# CYAN_EVSE_Logic_board_v1_3.net
KiCad netlist of a schematic drawn in Altium Designer
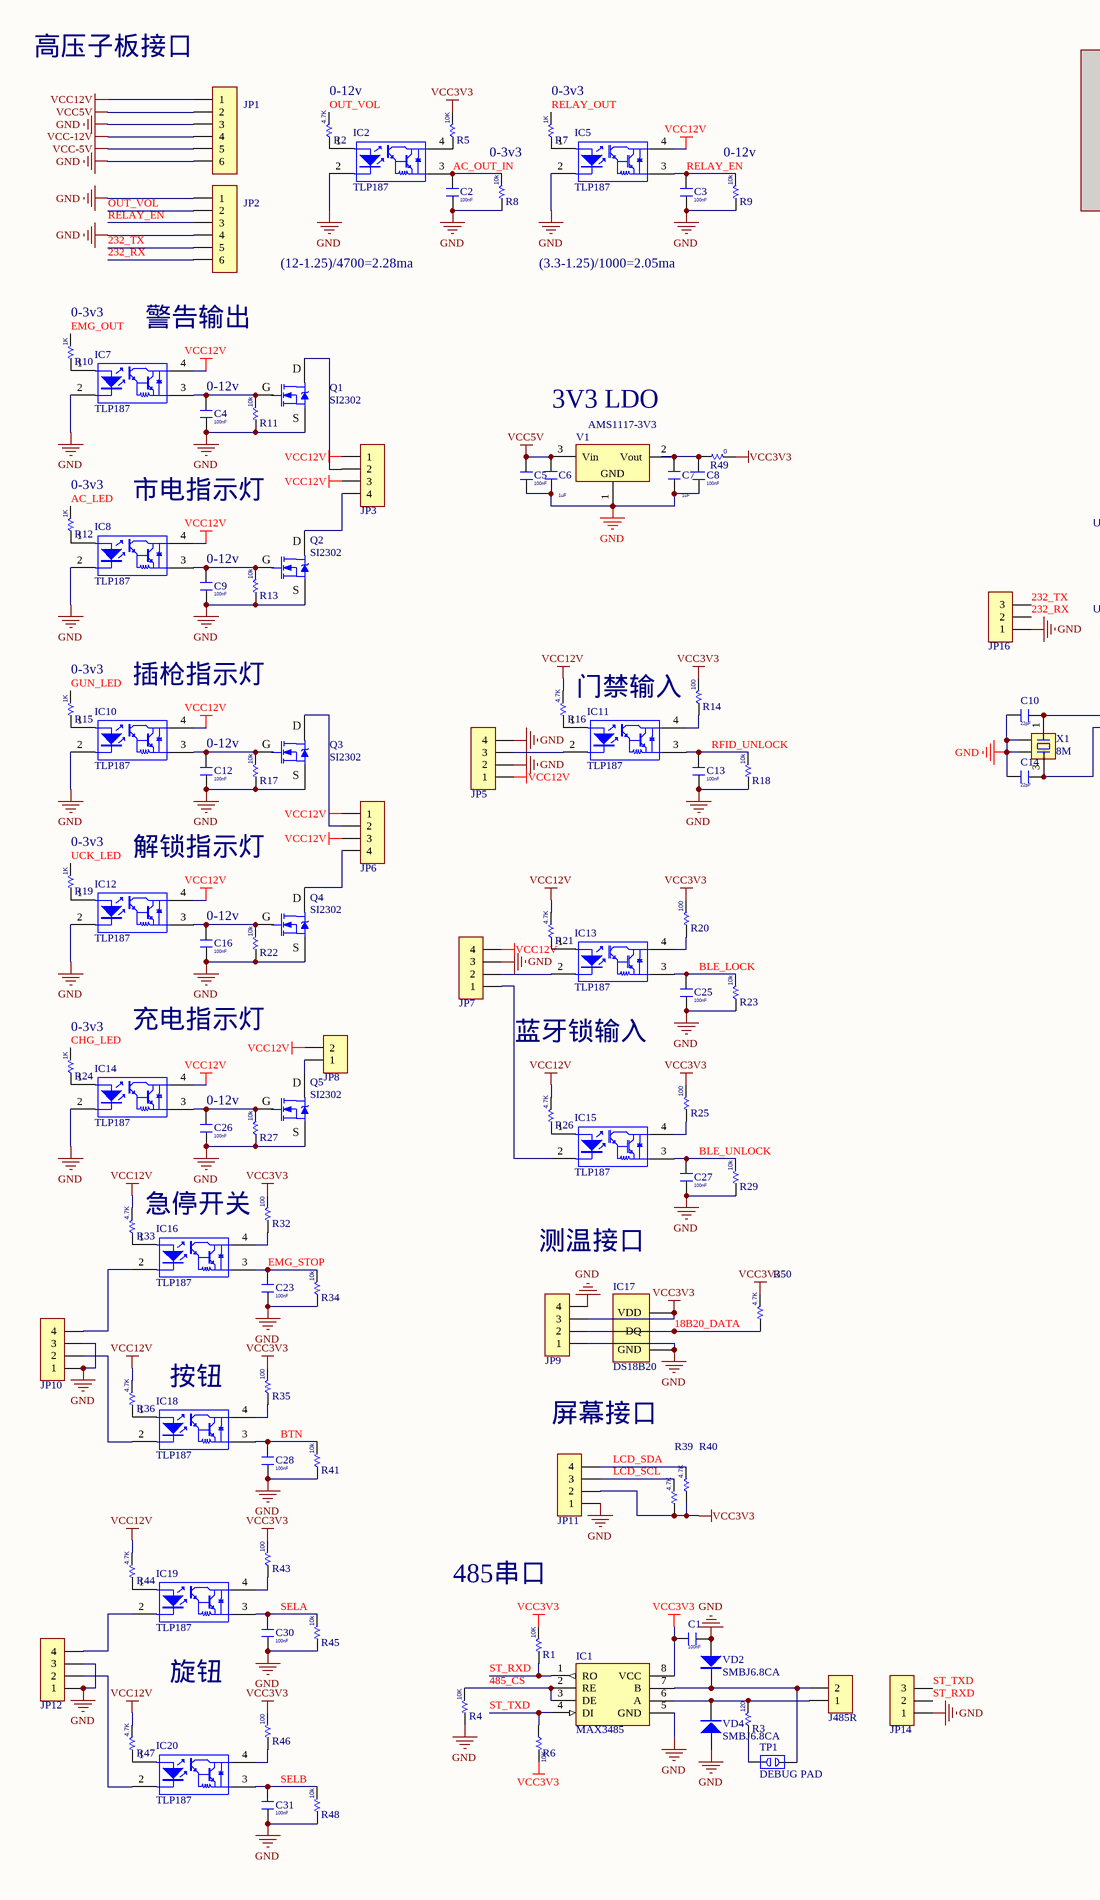
[diagram p0: CYAN_EVSE_Logic_board_v1.3.SchDoc, left]
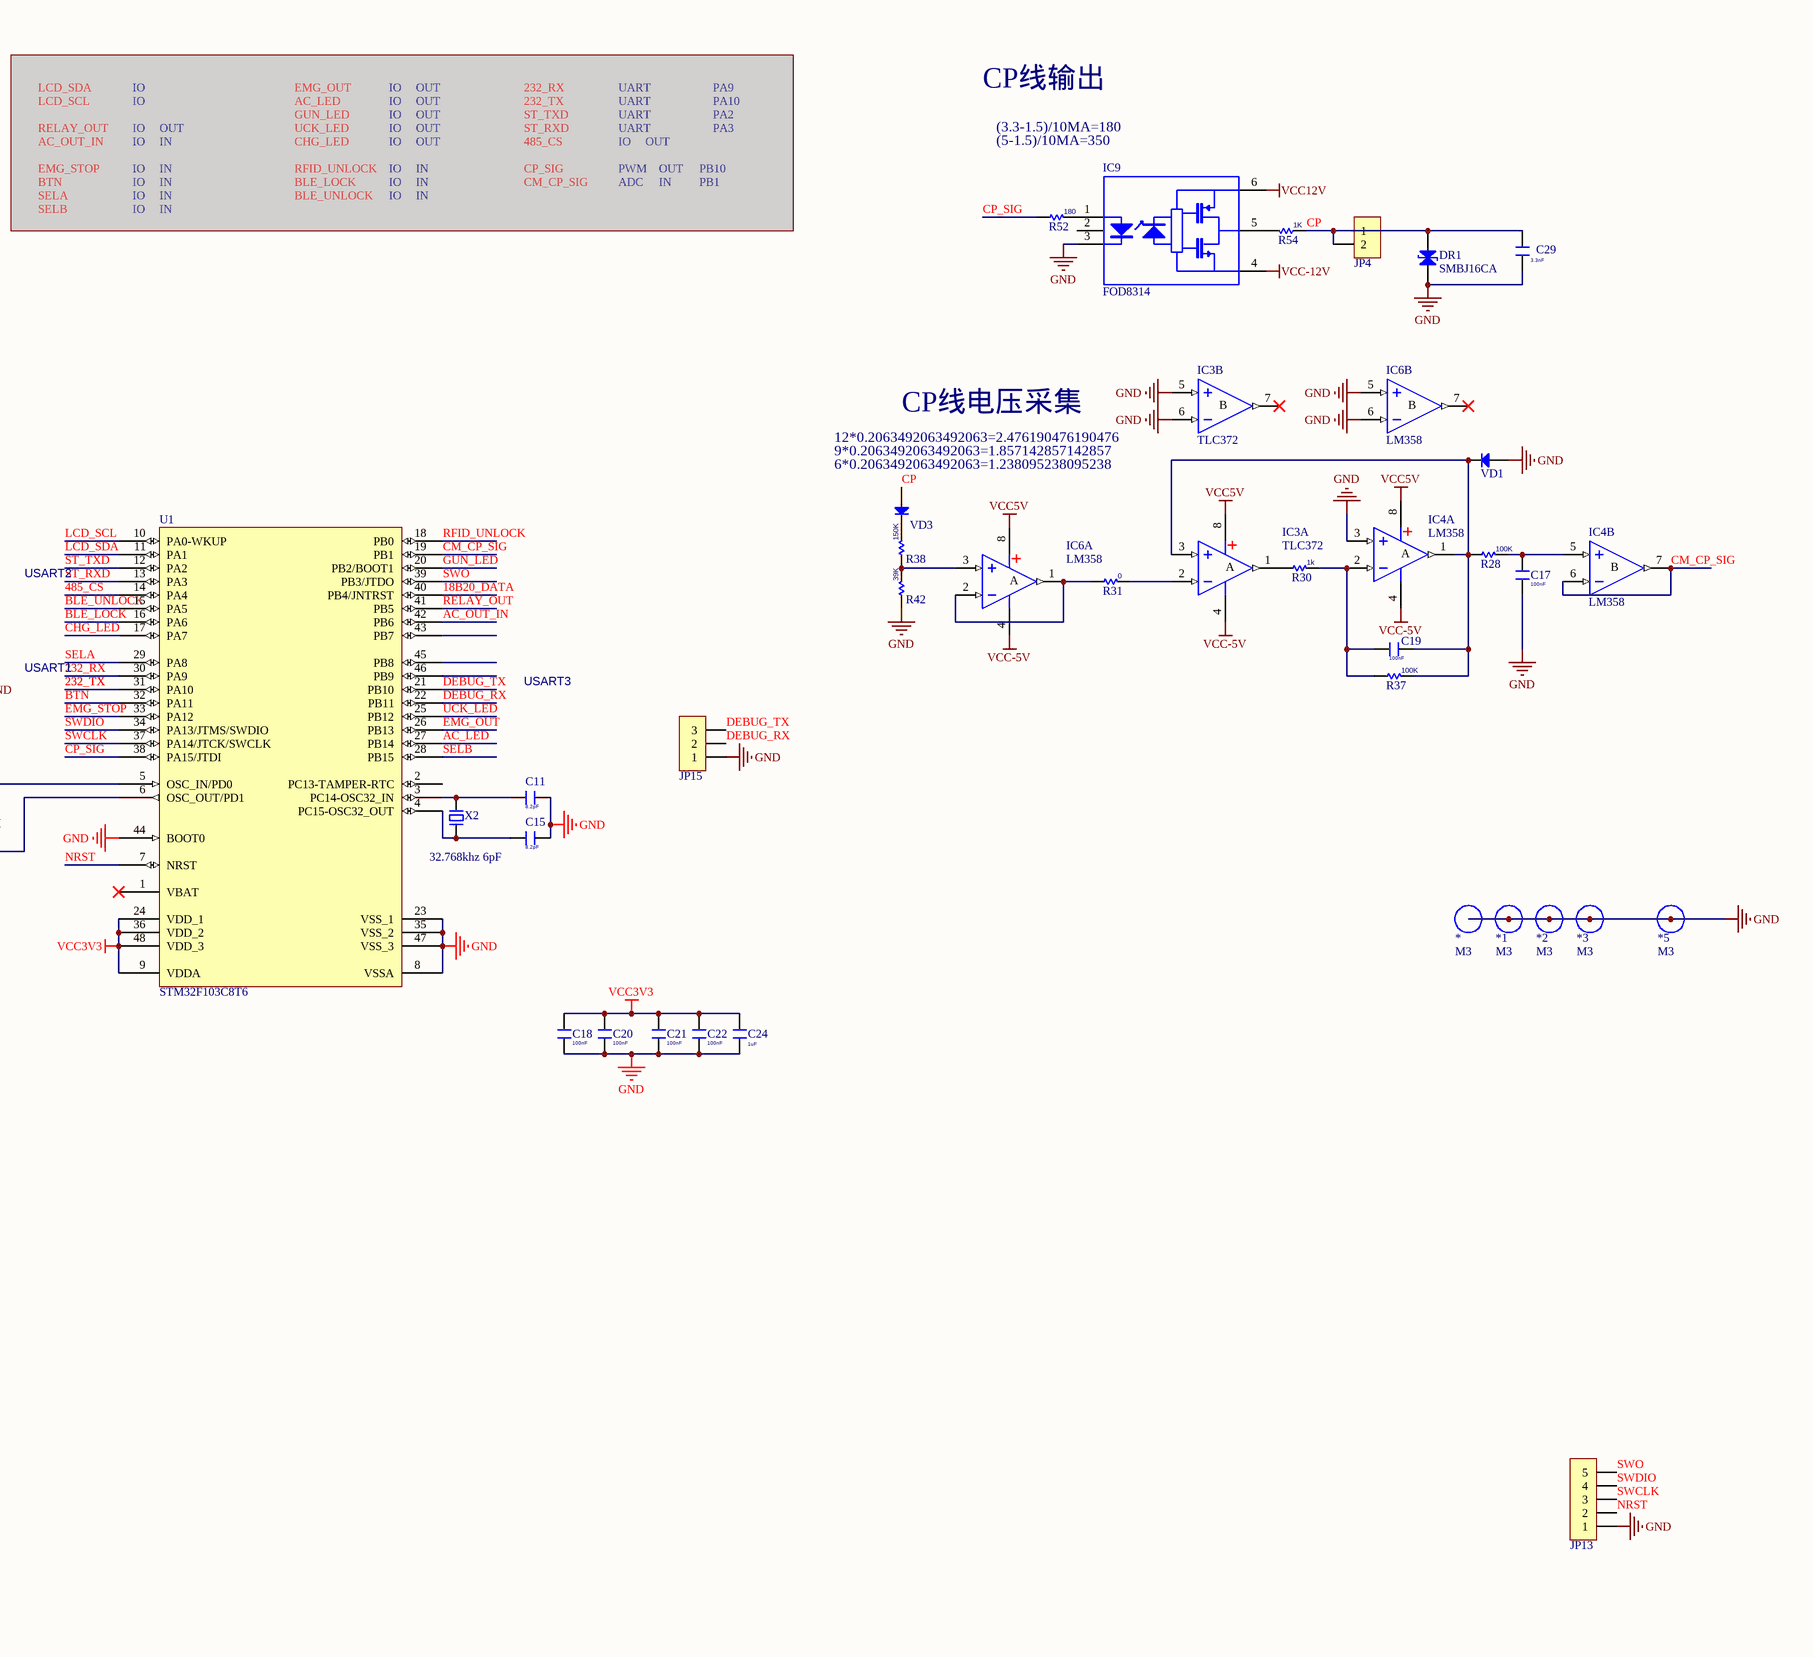
[diagram p1: CYAN_EVSE_Logic_board_v1.3.SchDoc, right]

(export (version "E")
  (design (tool "Eeschema 10.0.6"))
  (components
    (comp (ref "*")
      (value "M3")
      (footprint "M3 125X300")
      (description "铜柱孔")
      (libsource (lib "未分类器件") (part "M3"))
    )
    (comp (ref "*1")
      (value "M3")
      (footprint "M3 125X300")
      (description "铜柱孔")
      (libsource (lib "未分类器件") (part "M3"))
    )
    (comp (ref "*2")
      (value "M3")
      (footprint "M3 125X300")
      (description "铜柱孔")
      (libsource (lib "未分类器件") (part "M3"))
    )
    (comp (ref "*3")
      (value "M3")
      (footprint "M3 125X300")
      (description "铜柱孔")
      (libsource (lib "未分类器件") (part "M3"))
    )
    (comp (ref "*5")
      (value "M3")
      (footprint "M3 125X300")
      (description "铜柱孔")
      (libsource (lib "未分类器件") (part "M3"))
    )
    (comp (ref "C1")
      (value "100nF")
      (footprint "C 0805")
      (description "无极性贴片电容")
      (fields (field (name "VOLTAGE") "20V") (field (name "Comment") "C"))
      (libsource (lib "电阻-电容-电感") (part "C"))
    )
    (comp (ref "C2")
      (value "100nF")
      (footprint "C 0805")
      (description "无极性贴片电容")
      (fields (field (name "VOLTAGE") "20V") (field (name "Comment") "C"))
      (libsource (lib "电阻-电容-电感") (part "C"))
    )
    (comp (ref "C3")
      (value "100nF")
      (footprint "C 0805")
      (description "无极性贴片电容")
      (fields (field (name "VOLTAGE") "20V") (field (name "Comment") "C"))
      (libsource (lib "电阻-电容-电感") (part "C"))
    )
    (comp (ref "C4")
      (value "100nF")
      (footprint "C 0805")
      (description "无极性贴片电容")
      (fields (field (name "VOLTAGE") "20V") (field (name "Comment") "C"))
      (libsource (lib "电阻-电容-电感") (part "C"))
    )
    (comp (ref "C5")
      (value "100nF")
      (footprint "C 0805")
      (description "无极性贴片电容")
      (fields (field (name "VOLTAGE") "20V") (field (name "Comment") "C"))
      (libsource (lib "电阻-电容-电感") (part "C"))
    )
    (comp (ref "C6")
      (value "1uF")
      (footprint "C 0805")
      (description "无极性贴片电容")
      (fields (field (name "Comment") "C"))
      (libsource (lib "电阻-电容-电感") (part "C"))
    )
    (comp (ref "C7")
      (value "1uF")
      (footprint "C 0805")
      (description "无极性贴片电容")
      (fields (field (name "Comment") "C"))
      (libsource (lib "电阻-电容-电感") (part "C"))
    )
    (comp (ref "C8")
      (value "100nF")
      (footprint "C 0805")
      (description "无极性贴片电容")
      (fields (field (name "VOLTAGE") "20V") (field (name "Comment") "C"))
      (libsource (lib "电阻-电容-电感") (part "C"))
    )
    (comp (ref "C9")
      (value "100nF")
      (footprint "C 0805")
      (description "无极性贴片电容")
      (fields (field (name "VOLTAGE") "20V") (field (name "Comment") "C"))
      (libsource (lib "电阻-电容-电感") (part "C"))
    )
    (comp (ref "C10")
      (value "22pF")
      (footprint "C 0805")
      (description "无极性贴片电容")
      (fields (field (name "VOLTAGE") "20V") (field (name "Comment") "C"))
      (libsource (lib "电阻-电容-电感") (part "C"))
    )
    (comp (ref "C11")
      (value "8.2pF")
      (footprint "C 0805")
      (description "无极性贴片电容")
      (fields (field (name "VOLTAGE") "20V") (field (name "Comment") "C"))
      (libsource (lib "电阻-电容-电感") (part "C"))
    )
    (comp (ref "C12")
      (value "100nF")
      (footprint "C 0805")
      (description "无极性贴片电容")
      (fields (field (name "VOLTAGE") "20V") (field (name "Comment") "C"))
      (libsource (lib "电阻-电容-电感") (part "C"))
    )
    (comp (ref "C13")
      (value "100nF")
      (footprint "C 0805")
      (description "无极性贴片电容")
      (fields (field (name "VOLTAGE") "20V") (field (name "Comment") "C"))
      (libsource (lib "电阻-电容-电感") (part "C"))
    )
    (comp (ref "C14")
      (value "22pF")
      (footprint "C 0805")
      (description "无极性贴片电容")
      (fields (field (name "VOLTAGE") "20V") (field (name "Comment") "C"))
      (libsource (lib "电阻-电容-电感") (part "C"))
    )
    (comp (ref "C15")
      (value "8.2pF")
      (footprint "C 0805")
      (description "无极性贴片电容")
      (fields (field (name "VOLTAGE") "20V") (field (name "Comment") "C"))
      (libsource (lib "电阻-电容-电感") (part "C"))
    )
    (comp (ref "C16")
      (value "100nF")
      (footprint "C 0805")
      (description "无极性贴片电容")
      (fields (field (name "VOLTAGE") "20V") (field (name "Comment") "C"))
      (libsource (lib "电阻-电容-电感") (part "C"))
    )
    (comp (ref "C17")
      (value "100nF")
      (footprint "C 0805")
      (description "无极性贴片电容")
      (fields (field (name "VOLTAGE") "20V") (field (name "Comment") "C"))
      (libsource (lib "电阻-电容-电感") (part "C"))
    )
    (comp (ref "C18")
      (value "100nF")
      (footprint "C 0805")
      (description "无极性贴片电容")
      (fields (field (name "VOLTAGE") "20V") (field (name "Comment") "C"))
      (libsource (lib "电阻-电容-电感") (part "C"))
    )
    (comp (ref "C19")
      (value "100nF")
      (footprint "C 0805")
      (description "无极性贴片电容")
      (fields (field (name "VOLTAGE") "20V") (field (name "Comment") "C"))
      (libsource (lib "电阻-电容-电感") (part "C"))
    )
    (comp (ref "C20")
      (value "100nF")
      (footprint "C 0805")
      (description "无极性贴片电容")
      (fields (field (name "VOLTAGE") "20V") (field (name "Comment") "C"))
      (libsource (lib "电阻-电容-电感") (part "C"))
    )
    (comp (ref "C21")
      (value "100nF")
      (footprint "C 0805")
      (description "无极性贴片电容")
      (fields (field (name "VOLTAGE") "20V") (field (name "Comment") "C"))
      (libsource (lib "电阻-电容-电感") (part "C"))
    )
    (comp (ref "C22")
      (value "100nF")
      (footprint "C 0805")
      (description "无极性贴片电容")
      (fields (field (name "VOLTAGE") "20V") (field (name "Comment") "C"))
      (libsource (lib "电阻-电容-电感") (part "C"))
    )
    (comp (ref "C23")
      (value "100nF")
      (footprint "C 0805")
      (description "无极性贴片电容")
      (fields (field (name "VOLTAGE") "20V") (field (name "Comment") "C"))
      (libsource (lib "电阻-电容-电感") (part "C"))
    )
    (comp (ref "C24")
      (value "1uF")
      (footprint "C 0805")
      (description "无极性贴片电容")
      (fields (field (name "Comment") "C"))
      (libsource (lib "电阻-电容-电感") (part "C"))
    )
    (comp (ref "C25")
      (value "100nF")
      (footprint "C 0805")
      (description "无极性贴片电容")
      (fields (field (name "VOLTAGE") "20V") (field (name "Comment") "C"))
      (libsource (lib "电阻-电容-电感") (part "C"))
    )
    (comp (ref "C26")
      (value "100nF")
      (footprint "C 0805")
      (description "无极性贴片电容")
      (fields (field (name "VOLTAGE") "20V") (field (name "Comment") "C"))
      (libsource (lib "电阻-电容-电感") (part "C"))
    )
    (comp (ref "C27")
      (value "100nF")
      (footprint "C 0805")
      (description "无极性贴片电容")
      (fields (field (name "VOLTAGE") "20V") (field (name "Comment") "C"))
      (libsource (lib "电阻-电容-电感") (part "C"))
    )
    (comp (ref "C28")
      (value "100nF")
      (footprint "C 0805")
      (description "无极性贴片电容")
      (fields (field (name "VOLTAGE") "20V") (field (name "Comment") "C"))
      (libsource (lib "电阻-电容-电感") (part "C"))
    )
    (comp (ref "C29")
      (value "3.3nF")
      (footprint "C 1206")
      (description "无极性贴片电容")
      (fields (field (name "VOLTAGE") "50V") (field (name "Comment") "C"))
      (libsource (lib "电阻-电容-电感") (part "C"))
    )
    (comp (ref "C30")
      (value "100nF")
      (footprint "C 0805")
      (description "无极性贴片电容")
      (fields (field (name "VOLTAGE") "20V") (field (name "Comment") "C"))
      (libsource (lib "电阻-电容-电感") (part "C"))
    )
    (comp (ref "C31")
      (value "100nF")
      (footprint "C 0805")
      (description "无极性贴片电容")
      (fields (field (name "VOLTAGE") "20V") (field (name "Comment") "C"))
      (libsource (lib "电阻-电容-电感") (part "C"))
    )
    (comp (ref "DR1")
      (value "SMBJ16CA")
      (footprint "SMB")
      (description "瞬态电压抑制二极管")
      (libsource (lib "二极管-整流桥") (part "DR"))
    )
    (comp (ref "IC1")
      (value "MAX3485")
      (footprint "SOP8_N")
      (description "RS485总线收发芯片")
      (libsource (lib "IC芯片") (part "MAX487"))
    )
    (comp (ref "IC2")
      (value "TLP187")
      (footprint "SOP6_4.6MM_W1.27_4PIN_N")
      (description "达林顿输出光耦")
      (libsource (lib "传感元件") (part "TLP187"))
    )
    (comp (ref "IC3")
      (value "TLC372")
      (footprint "SOP8_N")
      (description "双路电压比较,MOS下臂输出")
      (libsource (lib "IC芯片") (part "TLC372"))
    )
    (comp (ref "IC4")
      (value "LM358")
      (footprint "SOP8_N")
      (description "双路运放")
      (libsource (lib "IC芯片") (part "LM358"))
    )
    (comp (ref "IC5")
      (value "TLP187")
      (footprint "SOP6_4.6MM_W1.27_4PIN_N")
      (description "达林顿输出光耦")
      (libsource (lib "传感元件") (part "TLP187"))
    )
    (comp (ref "IC6")
      (value "LM358")
      (footprint "SOP8_N")
      (description "双路运放")
      (libsource (lib "IC芯片") (part "LM358"))
    )
    (comp (ref "IC7")
      (value "TLP187")
      (footprint "SOP6_4.6MM_W1.27_4PIN_N")
      (description "达林顿输出光耦")
      (libsource (lib "传感元件") (part "TLP187"))
    )
    (comp (ref "IC8")
      (value "TLP187")
      (footprint "SOP6_4.6MM_W1.27_4PIN_N")
      (description "达林顿输出光耦")
      (libsource (lib "传感元件") (part "TLP187"))
    )
    (comp (ref "IC9")
      (value "FOD8314")
      (footprint "SOP6_7MM_WIDE_LEAD_N")
      (description "MOSFET/IGBT 驱动光耦，15-30v 1a")
      (libsource (lib "传感元件") (part "FOD8314"))
    )
    (comp (ref "IC10")
      (value "TLP187")
      (footprint "SOP6_4.6MM_W1.27_4PIN_N")
      (description "达林顿输出光耦")
      (libsource (lib "传感元件") (part "TLP187"))
    )
    (comp (ref "IC11")
      (value "TLP187")
      (footprint "SOP6_4.6MM_W1.27_4PIN_N")
      (description "达林顿输出光耦")
      (libsource (lib "传感元件") (part "TLP187"))
    )
    (comp (ref "IC12")
      (value "TLP187")
      (footprint "SOP6_4.6MM_W1.27_4PIN_N")
      (description "达林顿输出光耦")
      (libsource (lib "传感元件") (part "TLP187"))
    )
    (comp (ref "IC13")
      (value "TLP187")
      (footprint "SOP6_4.6MM_W1.27_4PIN_N")
      (description "达林顿输出光耦")
      (libsource (lib "传感元件") (part "TLP187"))
    )
    (comp (ref "IC14")
      (value "TLP187")
      (footprint "SOP6_4.6MM_W1.27_4PIN_N")
      (description "达林顿输出光耦")
      (libsource (lib "传感元件") (part "TLP187"))
    )
    (comp (ref "IC15")
      (value "TLP187")
      (footprint "SOP6_4.6MM_W1.27_4PIN_N")
      (description "达林顿输出光耦")
      (libsource (lib "传感元件") (part "TLP187"))
    )
    (comp (ref "IC16")
      (value "TLP187")
      (footprint "SOP6_4.6MM_W1.27_4PIN_N")
      (description "达林顿输出光耦")
      (libsource (lib "传感元件") (part "TLP187"))
    )
    (comp (ref "IC17")
      (value "DS18B20")
      (footprint "TO92A")
      (description "数字温度计")
      (libsource (lib "IC芯片") (part "DS18B20"))
    )
    (comp (ref "IC18")
      (value "TLP187")
      (footprint "SOP6_4.6MM_W1.27_4PIN_N")
      (description "达林顿输出光耦")
      (libsource (lib "传感元件") (part "TLP187"))
    )
    (comp (ref "IC19")
      (value "TLP187")
      (footprint "SOP6_4.6MM_W1.27_4PIN_N")
      (description "达林顿输出光耦")
      (libsource (lib "传感元件") (part "TLP187"))
    )
    (comp (ref "IC20")
      (value "TLP187")
      (footprint "SOP6_4.6MM_W1.27_4PIN_N")
      (description "达林顿输出光耦")
      (libsource (lib "传感元件") (part "TLP187"))
    )
    (comp (ref "J485R")
      (value "HDR-1X2")
      (footprint "MC 1,5/ 2-G-3,81")
      (description "2P接插件")
      (libsource (lib "接插件") (part "Header 2"))
    )
    (comp (ref "JP1")
      (value "HDR-1X6")
      (footprint "XH2.54-6P")
      (description "6P接插件")
      (libsource (lib "接插件") (part "Header 6"))
    )
    (comp (ref "JP2")
      (value "HDR-1X6")
      (footprint "XH2.54-6P")
      (description "6P接插件")
      (libsource (lib "接插件") (part "Header 6"))
    )
    (comp (ref "JP3")
      (value "HDR-1X4")
      (footprint "MC 1,5/ 4-G-3,81")
      (description "4P接插件")
      (libsource (lib "") (part "Header 4_1"))
    )
    (comp (ref "JP4")
      (value "HDR-1X2")
      (footprint "MC 1,5/ 2-G-3,81")
      (description "2P接插件")
      (libsource (lib "") (part "Header 2_1"))
    )
    (comp (ref "JP5")
      (value "HDR-1X4")
      (footprint "MC 1,5/ 4-G-3,81")
      (description "4P接插件")
      (libsource (lib "接插件") (part "Header 4"))
    )
    (comp (ref "JP6")
      (value "HDR-1X4")
      (footprint "MC 1,5/ 4-G-3,81")
      (description "4P接插件")
      (libsource (lib "") (part "Header 4_1"))
    )
    (comp (ref "JP7")
      (value "HDR-1X4")
      (footprint "MC 1,5/ 4-G-3,81")
      (description "4P接插件")
      (libsource (lib "接插件") (part "Header 4"))
    )
    (comp (ref "JP8")
      (value "HDR-1X2")
      (footprint "MC 1,5/ 2-G-3,81")
      (description "2P接插件")
      (libsource (lib "接插件") (part "Header 2"))
    )
    (comp (ref "JP9")
      (value "HDR-1X4")
      (footprint "MC 1,5/ 4-G-3,81")
      (description "4P接插件")
      (libsource (lib "接插件") (part "Header 4"))
    )
    (comp (ref "JP10")
      (value "HDR-1X4")
      (footprint "MC 1,5/ 4-G-3,81")
      (description "4P接插件")
      (libsource (lib "接插件") (part "Header 4"))
    )
    (comp (ref "JP11")
      (value "HDR-1X4")
      (footprint "XH2.54-4P")
      (description "4P接插件")
      (libsource (lib "接插件") (part "Header 4"))
    )
    (comp (ref "JP12")
      (value "HDR-1X4")
      (footprint "MC 1,5/ 4-G-3,81")
      (description "4P接插件")
      (libsource (lib "接插件") (part "Header 4"))
    )
    (comp (ref "JP13")
      (value "HDR-1X5")
      (footprint "HDR-1X5")
      (description "5P接插件")
      (libsource (lib "接插件") (part "Header 5"))
    )
    (comp (ref "JP14")
      (value "HDR-1X3")
      (footprint "HDR-1X3")
      (description "3P接插件")
      (libsource (lib "接插件") (part "Header 3"))
    )
    (comp (ref "JP15")
      (value "HDR-1X3")
      (footprint "HDR-1X3")
      (description "3P接插件")
      (libsource (lib "接插件") (part "Header 3"))
    )
    (comp (ref "JP16")
      (value "HDR-1X3")
      (footprint "HDR-1X3")
      (description "3P接插件")
      (libsource (lib "接插件") (part "Header 3"))
    )
    (comp (ref "Q1")
      (value "SI2302")
      (footprint "SOT23-3N")
      (description "N沟道场效应管")
      (libsource (lib "场效应管-可控硅") (part "SI2302"))
    )
    (comp (ref "Q2")
      (value "SI2302")
      (footprint "SOT23-3N")
      (description "N沟道场效应管")
      (libsource (lib "场效应管-可控硅") (part "SI2302"))
    )
    (comp (ref "Q3")
      (value "SI2302")
      (footprint "SOT23-3N")
      (description "N沟道场效应管")
      (libsource (lib "场效应管-可控硅") (part "SI2302"))
    )
    (comp (ref "Q4")
      (value "SI2302")
      (footprint "SOT23-3N")
      (description "N沟道场效应管")
      (libsource (lib "场效应管-可控硅") (part "SI2302"))
    )
    (comp (ref "Q5")
      (value "SI2302")
      (footprint "SOT23-3N")
      (description "N沟道场效应管")
      (libsource (lib "场效应管-可控硅") (part "SI2302"))
    )
    (comp (ref "R1")
      (value "10K")
      (footprint "R 0805")
      (description "贴片电阻")
      (fields (field (name "Comment") "R"))
      (libsource (lib "电阻-电容-电感") (part "R"))
    )
    (comp (ref "R2")
      (value "4.7K")
      (footprint "R 0805")
      (description "贴片电阻")
      (fields (field (name "Comment") "R"))
      (libsource (lib "电阻-电容-电感") (part "R"))
    )
    (comp (ref "R3")
      (value "120")
      (footprint "R 1206")
      (description "贴片电阻")
      (fields (field (name "Comment") "R"))
      (libsource (lib "电阻-电容-电感") (part "R"))
    )
    (comp (ref "R4")
      (value "10K")
      (footprint "R 0805")
      (description "贴片电阻")
      (fields (field (name "Comment") "R"))
      (libsource (lib "电阻-电容-电感") (part "R"))
    )
    (comp (ref "R5")
      (value "10K")
      (footprint "R 0805")
      (description "贴片电阻")
      (fields (field (name "Comment") "R"))
      (libsource (lib "电阻-电容-电感") (part "R"))
    )
    (comp (ref "R6")
      (value "10K")
      (footprint "R 0805")
      (description "贴片电阻")
      (fields (field (name "Comment") "R"))
      (libsource (lib "电阻-电容-电感") (part "R"))
    )
    (comp (ref "R7")
      (value "1K")
      (footprint "R 0805")
      (description "贴片电阻")
      (fields (field (name "Comment") "R"))
      (libsource (lib "电阻-电容-电感") (part "R"))
    )
    (comp (ref "R8")
      (value "10k")
      (footprint "R 0805")
      (description "贴片电阻")
      (fields (field (name "Comment") "R"))
      (libsource (lib "电阻-电容-电感") (part "R"))
    )
    (comp (ref "R9")
      (value "10k")
      (footprint "R 0805")
      (description "贴片电阻")
      (fields (field (name "Comment") "R"))
      (libsource (lib "电阻-电容-电感") (part "R"))
    )
    (comp (ref "R10")
      (value "1K")
      (footprint "R 0805")
      (description "贴片电阻")
      (fields (field (name "Comment") "R"))
      (libsource (lib "电阻-电容-电感") (part "R"))
    )
    (comp (ref "R11")
      (value "10k")
      (footprint "R 0805")
      (description "贴片电阻")
      (fields (field (name "Comment") "R"))
      (libsource (lib "电阻-电容-电感") (part "R"))
    )
    (comp (ref "R12")
      (value "1K")
      (footprint "R 0805")
      (description "贴片电阻")
      (fields (field (name "Comment") "R"))
      (libsource (lib "电阻-电容-电感") (part "R"))
    )
    (comp (ref "R13")
      (value "10k")
      (footprint "R 0805")
      (description "贴片电阻")
      (fields (field (name "Comment") "R"))
      (libsource (lib "电阻-电容-电感") (part "R"))
    )
    (comp (ref "R14")
      (value "100")
      (footprint "R 0805")
      (description "贴片电阻")
      (fields (field (name "Comment") "R"))
      (libsource (lib "电阻-电容-电感") (part "R"))
    )
    (comp (ref "R15")
      (value "1K")
      (footprint "R 0805")
      (description "贴片电阻")
      (fields (field (name "Comment") "R"))
      (libsource (lib "电阻-电容-电感") (part "R"))
    )
    (comp (ref "R16")
      (value "4.7K")
      (footprint "R 0805")
      (description "贴片电阻")
      (fields (field (name "Comment") "R"))
      (libsource (lib "电阻-电容-电感") (part "R"))
    )
    (comp (ref "R17")
      (value "10k")
      (footprint "R 0805")
      (description "贴片电阻")
      (fields (field (name "Comment") "R"))
      (libsource (lib "电阻-电容-电感") (part "R"))
    )
    (comp (ref "R18")
      (value "10k")
      (footprint "R 0805")
      (description "贴片电阻")
      (fields (field (name "Comment") "R"))
      (libsource (lib "电阻-电容-电感") (part "R"))
    )
    (comp (ref "R19")
      (value "1K")
      (footprint "R 0805")
      (description "贴片电阻")
      (fields (field (name "Comment") "R"))
      (libsource (lib "电阻-电容-电感") (part "R"))
    )
    (comp (ref "R20")
      (value "100")
      (footprint "R 0805")
      (description "贴片电阻")
      (fields (field (name "Comment") "R"))
      (libsource (lib "电阻-电容-电感") (part "R"))
    )
    (comp (ref "R21")
      (value "4.7K")
      (footprint "R 0805")
      (description "贴片电阻")
      (fields (field (name "Comment") "R"))
      (libsource (lib "电阻-电容-电感") (part "R"))
    )
    (comp (ref "R22")
      (value "10k")
      (footprint "R 0805")
      (description "贴片电阻")
      (fields (field (name "Comment") "R"))
      (libsource (lib "电阻-电容-电感") (part "R"))
    )
    (comp (ref "R23")
      (value "10k")
      (footprint "R 0805")
      (description "贴片电阻")
      (fields (field (name "Comment") "R"))
      (libsource (lib "电阻-电容-电感") (part "R"))
    )
    (comp (ref "R24")
      (value "1K")
      (footprint "R 0805")
      (description "贴片电阻")
      (fields (field (name "Comment") "R"))
      (libsource (lib "电阻-电容-电感") (part "R"))
    )
    (comp (ref "R25")
      (value "100")
      (footprint "R 0805")
      (description "贴片电阻")
      (fields (field (name "Comment") "R"))
      (libsource (lib "电阻-电容-电感") (part "R"))
    )
    (comp (ref "R26")
      (value "4.7K")
      (footprint "R 0805")
      (description "贴片电阻")
      (fields (field (name "Comment") "R"))
      (libsource (lib "电阻-电容-电感") (part "R"))
    )
    (comp (ref "R27")
      (value "10k")
      (footprint "R 0805")
      (description "贴片电阻")
      (fields (field (name "Comment") "R"))
      (libsource (lib "电阻-电容-电感") (part "R"))
    )
    (comp (ref "R28")
      (value "100K")
      (footprint "R 0805")
      (description "贴片电阻")
      (fields (field (name "Comment") "R"))
      (libsource (lib "电阻-电容-电感") (part "R"))
    )
    (comp (ref "R29")
      (value "10k")
      (footprint "R 0805")
      (description "贴片电阻")
      (fields (field (name "Comment") "R"))
      (libsource (lib "电阻-电容-电感") (part "R"))
    )
    (comp (ref "R30")
      (value "1k")
      (footprint "R 0805")
      (description "贴片电阻")
      (fields (field (name "Comment") "R"))
      (libsource (lib "电阻-电容-电感") (part "R"))
    )
    (comp (ref "R31")
      (value "0")
      (footprint "R 0805")
      (description "贴片电阻")
      (fields (field (name "Comment") "R"))
      (libsource (lib "电阻-电容-电感") (part "R"))
    )
    (comp (ref "R32")
      (value "100")
      (footprint "R 0805")
      (description "贴片电阻")
      (fields (field (name "Comment") "R"))
      (libsource (lib "电阻-电容-电感") (part "R"))
    )
    (comp (ref "R33")
      (value "4.7K")
      (footprint "R 0805")
      (description "贴片电阻")
      (fields (field (name "Comment") "R"))
      (libsource (lib "电阻-电容-电感") (part "R"))
    )
    (comp (ref "R34")
      (value "10k")
      (footprint "R 0805")
      (description "贴片电阻")
      (fields (field (name "Comment") "R"))
      (libsource (lib "电阻-电容-电感") (part "R"))
    )
    (comp (ref "R35")
      (value "100")
      (footprint "R 0805")
      (description "贴片电阻")
      (fields (field (name "Comment") "R"))
      (libsource (lib "电阻-电容-电感") (part "R"))
    )
    (comp (ref "R36")
      (value "4.7K")
      (footprint "R 0805")
      (description "贴片电阻")
      (fields (field (name "Comment") "R"))
      (libsource (lib "电阻-电容-电感") (part "R"))
    )
    (comp (ref "R37")
      (value "100K")
      (footprint "R 0805")
      (description "贴片电阻")
      (fields (field (name "Comment") "R"))
      (libsource (lib "电阻-电容-电感") (part "R"))
    )
    (comp (ref "R38")
      (value "150K")
      (footprint "R 0805")
      (description "贴片电阻")
      (fields (field (name "Comment") "R"))
      (libsource (lib "电阻-电容-电感") (part "R"))
    )
    (comp (ref "R39")
      (value "4.7K")
      (footprint "R 0805")
      (description "贴片电阻")
      (fields (field (name "Comment") "R"))
      (libsource (lib "电阻-电容-电感") (part "R"))
    )
    (comp (ref "R40")
      (value "4.7K")
      (footprint "R 0805")
      (description "贴片电阻")
      (fields (field (name "Comment") "R"))
      (libsource (lib "电阻-电容-电感") (part "R"))
    )
    (comp (ref "R41")
      (value "10k")
      (footprint "R 0805")
      (description "贴片电阻")
      (fields (field (name "Comment") "R"))
      (libsource (lib "电阻-电容-电感") (part "R"))
    )
    (comp (ref "R42")
      (value "39K")
      (footprint "R 0805")
      (description "贴片电阻")
      (fields (field (name "Comment") "R"))
      (libsource (lib "电阻-电容-电感") (part "R"))
    )
    (comp (ref "R43")
      (value "100")
      (footprint "R 0805")
      (description "贴片电阻")
      (fields (field (name "Comment") "R"))
      (libsource (lib "电阻-电容-电感") (part "R"))
    )
    (comp (ref "R44")
      (value "4.7K")
      (footprint "R 0805")
      (description "贴片电阻")
      (fields (field (name "Comment") "R"))
      (libsource (lib "电阻-电容-电感") (part "R"))
    )
    (comp (ref "R45")
      (value "10k")
      (footprint "R 0805")
      (description "贴片电阻")
      (fields (field (name "Comment") "R"))
      (libsource (lib "电阻-电容-电感") (part "R"))
    )
    (comp (ref "R46")
      (value "100")
      (footprint "R 0805")
      (description "贴片电阻")
      (fields (field (name "Comment") "R"))
      (libsource (lib "电阻-电容-电感") (part "R"))
    )
    (comp (ref "R47")
      (value "4.7K")
      (footprint "R 0805")
      (description "贴片电阻")
      (fields (field (name "Comment") "R"))
      (libsource (lib "电阻-电容-电感") (part "R"))
    )
    (comp (ref "R48")
      (value "10k")
      (footprint "R 0805")
      (description "贴片电阻")
      (fields (field (name "Comment") "R"))
      (libsource (lib "电阻-电容-电感") (part "R"))
    )
    (comp (ref "R49")
      (value "0")
      (footprint "R 0805")
      (description "贴片电阻")
      (fields (field (name "Comment") "R"))
      (libsource (lib "电阻-电容-电感") (part "R"))
    )
    (comp (ref "R50")
      (value "4.7K")
      (footprint "R 0805")
      (description "贴片电阻")
      (fields (field (name "Comment") "R"))
      (libsource (lib "电阻-电容-电感") (part "R"))
    )
    (comp (ref "R52")
      (value "180")
      (footprint "R 0805")
      (description "贴片电阻")
      (fields (field (name "Comment") "R"))
      (libsource (lib "电阻-电容-电感") (part "R"))
    )
    (comp (ref "R54")
      (value "1K")
      (footprint "R 1206")
      (description "贴片电阻")
      (fields (field (name "Comment") "R"))
      (libsource (lib "电阻-电容-电感") (part "R"))
    )
    (comp (ref "TP1")
      (value "DEBUG PAD")
      (footprint "DEBUG PAD2")
      (description "调试断点焊盘")
      (libsource (lib "未分类器件") (part "DEBUG"))
    )
    (comp (ref "U1")
      (value "STM32F103C8T6")
      (footprint "LQFP48 7X7_M")
      (description "Flaah:64/RAM:20/IO:36")
      (libsource (lib "STM32系列单片机") (part "STM32F103C8T6"))
    )
    (comp (ref "V1")
      (value "AMS1117-3V3")
      (footprint "SOT223_L")
      (description "三端稳压芯片")
      (libsource (lib "IC芯片") (part "AMS1117"))
    )
    (comp (ref "VD1")
      (value "1N4148")
      (footprint "SOD-323")
      (description "高速开关二极管")
      (libsource (lib "二极管-整流桥") (part "1N4148"))
    )
    (comp (ref "VD2")
      (value "SMBJ6.8CA")
      (footprint "SMB")
      (description "肖特基二极管")
      (libsource (lib "二极管-整流桥") (part "SS14"))
    )
    (comp (ref "VD3")
      (value "1N4148")
      (footprint "SOD-323")
      (description "高速开关二极管")
      (libsource (lib "二极管-整流桥") (part "1N4148"))
    )
    (comp (ref "VD4")
      (value "SMBJ6.8CA")
      (footprint "SMB")
      (description "肖特基二极管")
      (libsource (lib "二极管-整流桥") (part "SS14"))
    )
    (comp (ref "X1")
      (value "8M")
      (footprint "XTAL-3225")
      (description "4脚晶振")
      (libsource (lib "保险丝-晶振") (part "XTAL-4"))
    )
    (comp (ref "X2")
      (value "32.768khz 6pF")
      (footprint "XTAL-3215")
      (description "2脚晶振")
      (libsource (lib "保险丝-晶振") (part "XTAL-2"))
    )
  )
  (nets
    (net (code "1") (name "/18B20_DATA") (class "Default")
      (node (ref "IC17") (pin "2") (pinfunction "DQ_2") (pintype "passive"))
      (node (ref "JP9") (pin "2") (pinfunction "2_2") (pintype "passive"))
      (node (ref "R50") (pin "1") (pinfunction "1_1") (pintype "passive"))
      (node (ref "U1") (pin "40") (pinfunction "PB4/JNTRST_40") (pintype "bidirectional"))
    )
    (net (code "2") (name "/232_RX") (class "Default")
      (node (ref "JP16") (pin "2") (pinfunction "2_2") (pintype "passive"))
      (node (ref "JP2") (pin "6") (pinfunction "6_6") (pintype "passive"))
      (node (ref "U1") (pin "30") (pinfunction "PA9_30") (pintype "bidirectional"))
    )
    (net (code "3") (name "/232_TX") (class "Default")
      (node (ref "JP16") (pin "3") (pinfunction "3_3") (pintype "passive"))
      (node (ref "JP2") (pin "5") (pinfunction "5_5") (pintype "passive"))
      (node (ref "U1") (pin "31") (pinfunction "PA10_31") (pintype "bidirectional"))
    )
    (net (code "4") (name "/485_CS") (class "Default")
      (node (ref "IC1") (pin "2") (pinfunction "RE_2") (pintype "passive"))
      (node (ref "IC1") (pin "3") (pinfunction "DE_3") (pintype "passive"))
      (node (ref "R4") (pin "2") (pinfunction "2_2") (pintype "passive"))
      (node (ref "U1") (pin "14") (pinfunction "PA4_14") (pintype "bidirectional"))
    )
    (net (code "5") (name "/AC_LED") (class "Default")
      (node (ref "R12") (pin "2") (pinfunction "2_2") (pintype "passive"))
      (node (ref "U1") (pin "27") (pinfunction "PB14_27") (pintype "bidirectional"))
    )
    (net (code "6") (name "/AC_OUT_IN") (class "Default")
      (node (ref "C2") (pin "2") (pinfunction "2_2") (pintype "passive"))
      (node (ref "IC2") (pin "3") (pinfunction "E_3") (pintype "passive"))
      (node (ref "R8") (pin "2") (pinfunction "2_2") (pintype "passive"))
      (node (ref "U1") (pin "42") (pinfunction "PB6_42") (pintype "bidirectional"))
    )
    (net (code "7") (name "/BLE_LOCK") (class "Default")
      (node (ref "C25") (pin "2") (pinfunction "2_2") (pintype "passive"))
      (node (ref "IC13") (pin "3") (pinfunction "E_3") (pintype "passive"))
      (node (ref "R23") (pin "2") (pinfunction "2_2") (pintype "passive"))
      (node (ref "U1") (pin "16") (pinfunction "PA6_16") (pintype "bidirectional"))
    )
    (net (code "8") (name "/BLE_UNLOCK") (class "Default")
      (node (ref "C27") (pin "2") (pinfunction "2_2") (pintype "passive"))
      (node (ref "IC15") (pin "3") (pinfunction "E_3") (pintype "passive"))
      (node (ref "R29") (pin "2") (pinfunction "2_2") (pintype "passive"))
      (node (ref "U1") (pin "15") (pinfunction "PA5_15") (pintype "bidirectional"))
    )
    (net (code "9") (name "/BTN") (class "Default")
      (node (ref "C28") (pin "2") (pinfunction "2_2") (pintype "passive"))
      (node (ref "IC18") (pin "3") (pinfunction "E_3") (pintype "passive"))
      (node (ref "R41") (pin "2") (pinfunction "2_2") (pintype "passive"))
      (node (ref "U1") (pin "32") (pinfunction "PA11_32") (pintype "bidirectional"))
    )
    (net (code "10") (name "/CHG_LED") (class "Default")
      (node (ref "R24") (pin "2") (pinfunction "2_2") (pintype "passive"))
      (node (ref "U1") (pin "17") (pinfunction "PA7_17") (pintype "bidirectional"))
    )
    (net (code "11") (name "/CM_CP_SIG") (class "Default")
      (node (ref "IC4") (pin "6") (pinfunction "IN-_6") (pintype "input"))
      (node (ref "IC4") (pin "7") (pinfunction "OUT_7") (pintype "output"))
      (node (ref "U1") (pin "19") (pinfunction "PB1_19") (pintype "bidirectional"))
    )
    (net (code "12") (name "/CP") (class "Default")
      (node (ref "C29") (pin "2") (pinfunction "2_2") (pintype "passive"))
      (node (ref "DR1") (pin "1") (pinfunction "A_1") (pintype "passive"))
      (node (ref "JP4") (pin "1") (pinfunction "1_1") (pintype "passive"))
      (node (ref "JP4") (pin "2") (pinfunction "2_2") (pintype "passive"))
      (node (ref "R54") (pin "1") (pinfunction "1_1") (pintype "passive"))
      (node (ref "VD3") (pin "1") (pinfunction "A_1") (pintype "passive"))
    )
    (net (code "13") (name "/CP_SIG") (class "Default")
      (node (ref "R52") (pin "1") (pinfunction "1_1") (pintype "passive"))
      (node (ref "U1") (pin "38") (pinfunction "PA15/JTDI_38") (pintype "bidirectional"))
    )
    (net (code "14") (name "/DEBUG_RX") (class "Default")
      (node (ref "JP15") (pin "2") (pinfunction "2_2") (pintype "passive"))
      (node (ref "U1") (pin "22") (pinfunction "PB11_22") (pintype "bidirectional"))
    )
    (net (code "15") (name "/DEBUG_TX") (class "Default")
      (node (ref "JP15") (pin "3") (pinfunction "3_3") (pintype "passive"))
      (node (ref "U1") (pin "21") (pinfunction "PB10_21") (pintype "bidirectional"))
    )
    (net (code "16") (name "/EMG_OUT") (class "Default")
      (node (ref "R10") (pin "2") (pinfunction "2_2") (pintype "passive"))
      (node (ref "U1") (pin "26") (pinfunction "PB13_26") (pintype "bidirectional"))
    )
    (net (code "17") (name "/EMG_STOP") (class "Default")
      (node (ref "C23") (pin "2") (pinfunction "2_2") (pintype "passive"))
      (node (ref "IC16") (pin "3") (pinfunction "E_3") (pintype "passive"))
      (node (ref "R34") (pin "2") (pinfunction "2_2") (pintype "passive"))
      (node (ref "U1") (pin "33") (pinfunction "PA12_33") (pintype "bidirectional"))
    )
    (net (code "18") (name "/GUN_LED") (class "Default")
      (node (ref "R15") (pin "2") (pinfunction "2_2") (pintype "passive"))
      (node (ref "U1") (pin "20") (pinfunction "PB2/BOOT1_20") (pintype "bidirectional"))
    )
    (net (code "19") (name "/LCD_SCL") (class "Default")
      (node (ref "JP11") (pin "3") (pinfunction "3_3") (pintype "passive"))
      (node (ref "R39") (pin "2") (pinfunction "2_2") (pintype "passive"))
      (node (ref "U1") (pin "10") (pinfunction "PA0-WKUP_10") (pintype "bidirectional"))
    )
    (net (code "20") (name "/LCD_SDA") (class "Default")
      (node (ref "JP11") (pin "4") (pinfunction "4_4") (pintype "passive"))
      (node (ref "R40") (pin "2") (pinfunction "2_2") (pintype "passive"))
      (node (ref "U1") (pin "11") (pinfunction "PA1_11") (pintype "bidirectional"))
    )
    (net (code "21") (name "/NRST") (class "Default")
      (node (ref "JP13") (pin "2") (pinfunction "2_2") (pintype "passive"))
      (node (ref "U1") (pin "7") (pinfunction "NRST_7") (pintype "bidirectional"))
    )
    (net (code "22") (name "/OUT_VOL") (class "Default")
      (node (ref "JP2") (pin "2") (pinfunction "2_2") (pintype "passive"))
      (node (ref "R2") (pin "2") (pinfunction "2_2") (pintype "passive"))
    )
    (net (code "23") (name "/RELAY_EN") (class "Default")
      (node (ref "C3") (pin "2") (pinfunction "2_2") (pintype "passive"))
      (node (ref "IC5") (pin "3") (pinfunction "E_3") (pintype "passive"))
      (node (ref "JP2") (pin "3") (pinfunction "3_3") (pintype "passive"))
      (node (ref "R9") (pin "2") (pinfunction "2_2") (pintype "passive"))
    )
    (net (code "24") (name "/RELAY_OUT") (class "Default")
      (node (ref "R7") (pin "2") (pinfunction "2_2") (pintype "passive"))
      (node (ref "U1") (pin "41") (pinfunction "PB5_41") (pintype "bidirectional"))
    )
    (net (code "25") (name "/RFID_UNLOCK") (class "Default")
      (node (ref "C13") (pin "2") (pinfunction "2_2") (pintype "passive"))
      (node (ref "IC11") (pin "3") (pinfunction "E_3") (pintype "passive"))
      (node (ref "R18") (pin "2") (pinfunction "2_2") (pintype "passive"))
      (node (ref "U1") (pin "18") (pinfunction "PB0_18") (pintype "bidirectional"))
    )
    (net (code "26") (name "/SELA") (class "Default")
      (node (ref "C30") (pin "2") (pinfunction "2_2") (pintype "passive"))
      (node (ref "IC19") (pin "3") (pinfunction "E_3") (pintype "passive"))
      (node (ref "R45") (pin "2") (pinfunction "2_2") (pintype "passive"))
      (node (ref "U1") (pin "29") (pinfunction "PA8_29") (pintype "bidirectional"))
    )
    (net (code "27") (name "/SELB") (class "Default")
      (node (ref "C31") (pin "2") (pinfunction "2_2") (pintype "passive"))
      (node (ref "IC20") (pin "3") (pinfunction "E_3") (pintype "passive"))
      (node (ref "R48") (pin "2") (pinfunction "2_2") (pintype "passive"))
      (node (ref "U1") (pin "28") (pinfunction "PB15_28") (pintype "bidirectional"))
    )
    (net (code "28") (name "/ST_RXD") (class "Default")
      (node (ref "IC1") (pin "1") (pinfunction "RO_1") (pintype "output"))
      (node (ref "JP14") (pin "2") (pinfunction "2_2") (pintype "passive"))
      (node (ref "R1") (pin "1") (pinfunction "1_1") (pintype "passive"))
      (node (ref "U1") (pin "13") (pinfunction "PA3_13") (pintype "bidirectional"))
    )
    (net (code "29") (name "/ST_TXD") (class "Default")
      (node (ref "IC1") (pin "4") (pinfunction "DI_4") (pintype "input"))
      (node (ref "JP14") (pin "3") (pinfunction "3_3") (pintype "passive"))
      (node (ref "R6") (pin "1") (pinfunction "1_1") (pintype "passive"))
      (node (ref "U1") (pin "12") (pinfunction "PA2_12") (pintype "bidirectional"))
    )
    (net (code "30") (name "/SWCLK") (class "Default")
      (node (ref "JP13") (pin "3") (pinfunction "3_3") (pintype "passive"))
      (node (ref "U1") (pin "37") (pinfunction "PA14/JTCK/SWCLK_37") (pintype "bidirectional"))
    )
    (net (code "31") (name "/SWDIO") (class "Default")
      (node (ref "JP13") (pin "4") (pinfunction "4_4") (pintype "passive"))
      (node (ref "U1") (pin "34") (pinfunction "PA13/JTMS/SWDIO_34") (pintype "bidirectional"))
    )
    (net (code "32") (name "/SWO") (class "Default")
      (node (ref "JP13") (pin "5") (pinfunction "5_5") (pintype "passive"))
      (node (ref "U1") (pin "39") (pinfunction "PB3/JTDO_39") (pintype "bidirectional"))
    )
    (net (code "33") (name "/UCK_LED") (class "Default")
      (node (ref "R19") (pin "2") (pinfunction "2_2") (pintype "passive"))
      (node (ref "U1") (pin "25") (pinfunction "PB12_25") (pintype "bidirectional"))
    )
    (net (code "34") (name "GND") (class "Default")
      (node (ref "*") (pin "0") (pinfunction "0_0") (pintype "passive"))
      (node (ref "*1") (pin "0") (pinfunction "0_0") (pintype "passive"))
      (node (ref "*2") (pin "0") (pinfunction "0_0") (pintype "passive"))
      (node (ref "*3") (pin "0") (pinfunction "0_0") (pintype "passive"))
      (node (ref "*5") (pin "0") (pinfunction "0_0") (pintype "passive"))
      (node (ref "C1") (pin "1") (pinfunction "1_1") (pintype "passive"))
      (node (ref "C10") (pin "2") (pinfunction "2_2") (pintype "passive"))
      (node (ref "C11") (pin "1") (pinfunction "1_1") (pintype "passive"))
      (node (ref "C12") (pin "1") (pinfunction "1_1") (pintype "passive"))
      (node (ref "C13") (pin "1") (pinfunction "1_1") (pintype "passive"))
      (node (ref "C14") (pin "2") (pinfunction "2_2") (pintype "passive"))
      (node (ref "C15") (pin "1") (pinfunction "1_1") (pintype "passive"))
      (node (ref "C16") (pin "1") (pinfunction "1_1") (pintype "passive"))
      (node (ref "C17") (pin "2") (pinfunction "2_2") (pintype "passive"))
      (node (ref "C18") (pin "1") (pinfunction "1_1") (pintype "passive"))
      (node (ref "C2") (pin "1") (pinfunction "1_1") (pintype "passive"))
      (node (ref "C20") (pin "1") (pinfunction "1_1") (pintype "passive"))
      (node (ref "C21") (pin "1") (pinfunction "1_1") (pintype "passive"))
      (node (ref "C22") (pin "1") (pinfunction "1_1") (pintype "passive"))
      (node (ref "C23") (pin "1") (pinfunction "1_1") (pintype "passive"))
      (node (ref "C24") (pin "2") (pinfunction "2_2") (pintype "passive"))
      (node (ref "C25") (pin "1") (pinfunction "1_1") (pintype "passive"))
      (node (ref "C26") (pin "1") (pinfunction "1_1") (pintype "passive"))
      (node (ref "C27") (pin "1") (pinfunction "1_1") (pintype "passive"))
      (node (ref "C28") (pin "1") (pinfunction "1_1") (pintype "passive"))
      (node (ref "C29") (pin "1") (pinfunction "1_1") (pintype "passive"))
      (node (ref "C3") (pin "1") (pinfunction "1_1") (pintype "passive"))
      (node (ref "C30") (pin "1") (pinfunction "1_1") (pintype "passive"))
      (node (ref "C31") (pin "1") (pinfunction "1_1") (pintype "passive"))
      (node (ref "C4") (pin "1") (pinfunction "1_1") (pintype "passive"))
      (node (ref "C5") (pin "1") (pinfunction "1_1") (pintype "passive"))
      (node (ref "C6") (pin "2") (pinfunction "2_2") (pintype "passive"))
      (node (ref "C7") (pin "2") (pinfunction "2_2") (pintype "passive"))
      (node (ref "C8") (pin "1") (pinfunction "1_1") (pintype "passive"))
      (node (ref "C9") (pin "1") (pinfunction "1_1") (pintype "passive"))
      (node (ref "DR1") (pin "2") (pinfunction "K_2") (pintype "passive"))
      (node (ref "IC1") (pin "5") (pinfunction "GND_5") (pintype "passive"))
      (node (ref "IC10") (pin "2") (pinfunction "K_2") (pintype "passive"))
      (node (ref "IC12") (pin "2") (pinfunction "K_2") (pintype "passive"))
      (node (ref "IC14") (pin "2") (pinfunction "K_2") (pintype "passive"))
      (node (ref "IC17") (pin "1") (pinfunction "GND_1") (pintype "passive"))
      (node (ref "IC2") (pin "2") (pinfunction "K_2") (pintype "passive"))
      (node (ref "IC3") (pin "5") (pinfunction "IN+_5") (pintype "input"))
      (node (ref "IC3") (pin "6") (pinfunction "IN-_6") (pintype "input"))
      (node (ref "IC4") (pin "3") (pinfunction "IN+_3") (pintype "input"))
      (node (ref "IC5") (pin "2") (pinfunction "K_2") (pintype "passive"))
      (node (ref "IC6") (pin "5") (pinfunction "IN+_5") (pintype "input"))
      (node (ref "IC6") (pin "6") (pinfunction "IN-_6") (pintype "input"))
      (node (ref "IC7") (pin "2") (pinfunction "K_2") (pintype "passive"))
      (node (ref "IC8") (pin "2") (pinfunction "K_2") (pintype "passive"))
      (node (ref "IC9") (pin "3") (pinfunction "K_3") (pintype "passive"))
      (node (ref "JP1") (pin "3") (pinfunction "3_3") (pintype "passive"))
      (node (ref "JP1") (pin "6") (pinfunction "6_6") (pintype "passive"))
      (node (ref "JP10") (pin "1") (pinfunction "1_1") (pintype "passive"))
      (node (ref "JP10") (pin "3") (pinfunction "3_3") (pintype "passive"))
      (node (ref "JP11") (pin "1") (pinfunction "1_1") (pintype "passive"))
      (node (ref "JP12") (pin "1") (pinfunction "1_1") (pintype "passive"))
      (node (ref "JP12") (pin "3") (pinfunction "3_3") (pintype "passive"))
      (node (ref "JP13") (pin "1") (pinfunction "1_1") (pintype "passive"))
      (node (ref "JP14") (pin "1") (pinfunction "1_1") (pintype "passive"))
      (node (ref "JP15") (pin "1") (pinfunction "1_1") (pintype "passive"))
      (node (ref "JP16") (pin "1") (pinfunction "1_1") (pintype "passive"))
      (node (ref "JP2") (pin "1") (pinfunction "1_1") (pintype "passive"))
      (node (ref "JP2") (pin "4") (pinfunction "4_4") (pintype "passive"))
      (node (ref "JP5") (pin "2") (pinfunction "2_2") (pintype "passive"))
      (node (ref "JP5") (pin "4") (pinfunction "4_4") (pintype "passive"))
      (node (ref "JP7") (pin "3") (pinfunction "3_3") (pintype "passive"))
      (node (ref "JP9") (pin "1") (pinfunction "1_1") (pintype "passive"))
      (node (ref "JP9") (pin "4") (pinfunction "4_4") (pintype "passive"))
      (node (ref "Q1") (pin "2") (pinfunction "S_2") (pintype "passive"))
      (node (ref "Q2") (pin "2") (pinfunction "S_2") (pintype "passive"))
      (node (ref "Q3") (pin "2") (pinfunction "S_2") (pintype "passive"))
      (node (ref "Q4") (pin "2") (pinfunction "S_2") (pintype "passive"))
      (node (ref "Q5") (pin "2") (pinfunction "S_2") (pintype "passive"))
      (node (ref "R11") (pin "1") (pinfunction "1_1") (pintype "passive"))
      (node (ref "R13") (pin "1") (pinfunction "1_1") (pintype "passive"))
      (node (ref "R17") (pin "1") (pinfunction "1_1") (pintype "passive"))
      (node (ref "R18") (pin "1") (pinfunction "1_1") (pintype "passive"))
      (node (ref "R22") (pin "1") (pinfunction "1_1") (pintype "passive"))
      (node (ref "R23") (pin "1") (pinfunction "1_1") (pintype "passive"))
      (node (ref "R27") (pin "1") (pinfunction "1_1") (pintype "passive"))
      (node (ref "R29") (pin "1") (pinfunction "1_1") (pintype "passive"))
      (node (ref "R34") (pin "1") (pinfunction "1_1") (pintype "passive"))
      (node (ref "R4") (pin "1") (pinfunction "1_1") (pintype "passive"))
      (node (ref "R41") (pin "1") (pinfunction "1_1") (pintype "passive"))
      (node (ref "R42") (pin "1") (pinfunction "1_1") (pintype "passive"))
      (node (ref "R45") (pin "1") (pinfunction "1_1") (pintype "passive"))
      (node (ref "R48") (pin "1") (pinfunction "1_1") (pintype "passive"))
      (node (ref "R8") (pin "1") (pinfunction "1_1") (pintype "passive"))
      (node (ref "R9") (pin "1") (pinfunction "1_1") (pintype "passive"))
      (node (ref "U1") (pin "23") (pinfunction "VSS_1_23") (pintype "power_in"))
      (node (ref "U1") (pin "35") (pinfunction "VSS_2_35") (pintype "power_in"))
      (node (ref "U1") (pin "44") (pinfunction "BOOT0_44") (pintype "input"))
      (node (ref "U1") (pin "47") (pinfunction "VSS_3_47") (pintype "power_in"))
      (node (ref "U1") (pin "8") (pinfunction "VSSA_8") (pintype "power_in"))
      (node (ref "V1") (pin "1") (pinfunction "GND_1") (pintype "passive"))
      (node (ref "VD1") (pin "1") (pinfunction "A_1") (pintype "passive"))
      (node (ref "VD2") (pin "1") (pinfunction "A_1") (pintype "passive"))
      (node (ref "VD4") (pin "1") (pinfunction "A_1") (pintype "passive"))
      (node (ref "X1") (pin "2") (pinfunction "2_2") (pintype "passive"))
      (node (ref "X1") (pin "4") (pinfunction "4_4") (pintype "passive"))
    )
    (net (code "35") (name "Net-(IC1-A)") (class "Default")
      (node (ref "IC1") (pin "6") (pinfunction "A_6") (pintype "passive"))
      (node (ref "J485R") (pin "1") (pinfunction "1_1") (pintype "passive"))
      (node (ref "R3") (pin "2") (pinfunction "2_2") (pintype "passive"))
      (node (ref "VD4") (pin "2") (pinfunction "K_2") (pintype "passive"))
    )
    (net (code "36") (name "Net-(IC1-B)") (class "Default")
      (node (ref "IC1") (pin "7") (pinfunction "B_7") (pintype "passive"))
      (node (ref "J485R") (pin "2") (pinfunction "2_2") (pintype "passive"))
      (node (ref "TP1") (pin "2") (pinfunction "2_2") (pintype "passive"))
      (node (ref "VD2") (pin "2") (pinfunction "K_2") (pintype "passive"))
    )
    (net (code "37") (name "Net-(IC2-A)") (class "Default")
      (node (ref "IC2") (pin "1") (pinfunction "A_1") (pintype "passive"))
      (node (ref "R2") (pin "1") (pinfunction "1_1") (pintype "passive"))
    )
    (net (code "38") (name "Net-(IC2-C)") (class "Default")
      (node (ref "IC2") (pin "4") (pinfunction "C_4") (pintype "passive"))
      (node (ref "R5") (pin "1") (pinfunction "1_1") (pintype "passive"))
    )
    (net (code "39") (name "Net-(IC3A-IN+)") (class "Default")
      (node (ref "C19") (pin "1") (pinfunction "1_1") (pintype "passive"))
      (node (ref "IC3") (pin "3") (pinfunction "IN+_3") (pintype "input"))
      (node (ref "IC4") (pin "1") (pinfunction "OUT_1") (pintype "output"))
      (node (ref "R28") (pin "1") (pinfunction "1_1") (pintype "passive"))
      (node (ref "R37") (pin "2") (pinfunction "2_2") (pintype "passive"))
      (node (ref "VD1") (pin "2") (pinfunction "K_2") (pintype "passive"))
    )
    (net (code "40") (name "Net-(IC3A-IN-)") (class "Default")
      (node (ref "IC3") (pin "2") (pinfunction "IN-_2") (pintype "input"))
      (node (ref "R31") (pin "2") (pinfunction "2_2") (pintype "passive"))
    )
    (net (code "41") (name "Net-(IC3A-OUT)") (class "Default")
      (node (ref "IC3") (pin "1") (pinfunction "OUT_1") (pintype "output"))
      (node (ref "R30") (pin "1") (pinfunction "1_1") (pintype "passive"))
    )
    (net (code "42") (name "Net-(IC4A-IN-)") (class "Default")
      (node (ref "C19") (pin "2") (pinfunction "2_2") (pintype "passive"))
      (node (ref "IC4") (pin "2") (pinfunction "IN-_2") (pintype "input"))
      (node (ref "R30") (pin "2") (pinfunction "2_2") (pintype "passive"))
      (node (ref "R37") (pin "1") (pinfunction "1_1") (pintype "passive"))
    )
    (net (code "43") (name "Net-(IC4B-IN+)") (class "Default")
      (node (ref "C17") (pin "1") (pinfunction "1_1") (pintype "passive"))
      (node (ref "IC4") (pin "5") (pinfunction "IN+_5") (pintype "input"))
      (node (ref "R28") (pin "2") (pinfunction "2_2") (pintype "passive"))
    )
    (net (code "44") (name "Net-(IC5-A)") (class "Default")
      (node (ref "IC5") (pin "1") (pinfunction "A_1") (pintype "passive"))
      (node (ref "R7") (pin "1") (pinfunction "1_1") (pintype "passive"))
    )
    (net (code "45") (name "Net-(IC6A-IN+)") (class "Default")
      (node (ref "IC6") (pin "3") (pinfunction "IN+_3") (pintype "input"))
      (node (ref "R38") (pin "1") (pinfunction "1_1") (pintype "passive"))
      (node (ref "R42") (pin "2") (pinfunction "2_2") (pintype "passive"))
    )
    (net (code "46") (name "Net-(IC6A-IN-)") (class "Default")
      (node (ref "IC6") (pin "1") (pinfunction "OUT_1") (pintype "output"))
      (node (ref "IC6") (pin "2") (pinfunction "IN-_2") (pintype "input"))
      (node (ref "R31") (pin "1") (pinfunction "1_1") (pintype "passive"))
    )
    (net (code "47") (name "Net-(IC7-A)") (class "Default")
      (node (ref "IC7") (pin "1") (pinfunction "A_1") (pintype "passive"))
      (node (ref "R10") (pin "1") (pinfunction "1_1") (pintype "passive"))
    )
    (net (code "48") (name "Net-(IC7-E)") (class "Default")
      (node (ref "C4") (pin "2") (pinfunction "2_2") (pintype "passive"))
      (node (ref "IC7") (pin "3") (pinfunction "E_3") (pintype "passive"))
      (node (ref "Q1") (pin "1") (pinfunction "G_1") (pintype "passive"))
      (node (ref "R11") (pin "2") (pinfunction "2_2") (pintype "passive"))
    )
    (net (code "49") (name "Net-(IC8-A)") (class "Default")
      (node (ref "IC8") (pin "1") (pinfunction "A_1") (pintype "passive"))
      (node (ref "R12") (pin "1") (pinfunction "1_1") (pintype "passive"))
    )
    (net (code "50") (name "Net-(IC8-E)") (class "Default")
      (node (ref "C9") (pin "2") (pinfunction "2_2") (pintype "passive"))
      (node (ref "IC8") (pin "3") (pinfunction "E_3") (pintype "passive"))
      (node (ref "Q2") (pin "1") (pinfunction "G_1") (pintype "passive"))
      (node (ref "R13") (pin "2") (pinfunction "2_2") (pintype "passive"))
    )
    (net (code "51") (name "Net-(IC9-A)") (class "Default")
      (node (ref "IC9") (pin "1") (pinfunction "A_1") (pintype "passive"))
      (node (ref "R52") (pin "2") (pinfunction "2_2") (pintype "passive"))
    )
    (net (code "52") (name "Net-(IC9-OUT)") (class "Default")
      (node (ref "IC9") (pin "5") (pinfunction "OUT_5") (pintype "passive"))
      (node (ref "R54") (pin "2") (pinfunction "2_2") (pintype "passive"))
    )
    (net (code "53") (name "Net-(IC10-A)") (class "Default")
      (node (ref "IC10") (pin "1") (pinfunction "A_1") (pintype "passive"))
      (node (ref "R15") (pin "1") (pinfunction "1_1") (pintype "passive"))
    )
    (net (code "54") (name "Net-(IC10-E)") (class "Default")
      (node (ref "C12") (pin "2") (pinfunction "2_2") (pintype "passive"))
      (node (ref "IC10") (pin "3") (pinfunction "E_3") (pintype "passive"))
      (node (ref "Q3") (pin "1") (pinfunction "G_1") (pintype "passive"))
      (node (ref "R17") (pin "2") (pinfunction "2_2") (pintype "passive"))
    )
    (net (code "55") (name "Net-(IC11-A)") (class "Default")
      (node (ref "IC11") (pin "1") (pinfunction "A_1") (pintype "passive"))
      (node (ref "R16") (pin "1") (pinfunction "1_1") (pintype "passive"))
    )
    (net (code "56") (name "Net-(IC11-C)") (class "Default")
      (node (ref "IC11") (pin "4") (pinfunction "C_4") (pintype "passive"))
      (node (ref "R14") (pin "1") (pinfunction "1_1") (pintype "passive"))
    )
    (net (code "57") (name "Net-(IC11-K)") (class "Default")
      (node (ref "IC11") (pin "2") (pinfunction "K_2") (pintype "passive"))
      (node (ref "JP5") (pin "3") (pinfunction "3_3") (pintype "passive"))
    )
    (net (code "58") (name "Net-(IC12-A)") (class "Default")
      (node (ref "IC12") (pin "1") (pinfunction "A_1") (pintype "passive"))
      (node (ref "R19") (pin "1") (pinfunction "1_1") (pintype "passive"))
    )
    (net (code "59") (name "Net-(IC12-E)") (class "Default")
      (node (ref "C16") (pin "2") (pinfunction "2_2") (pintype "passive"))
      (node (ref "IC12") (pin "3") (pinfunction "E_3") (pintype "passive"))
      (node (ref "Q4") (pin "1") (pinfunction "G_1") (pintype "passive"))
      (node (ref "R22") (pin "2") (pinfunction "2_2") (pintype "passive"))
    )
    (net (code "60") (name "Net-(IC13-A)") (class "Default")
      (node (ref "IC13") (pin "1") (pinfunction "A_1") (pintype "passive"))
      (node (ref "R21") (pin "1") (pinfunction "1_1") (pintype "passive"))
    )
    (net (code "61") (name "Net-(IC13-C)") (class "Default")
      (node (ref "IC13") (pin "4") (pinfunction "C_4") (pintype "passive"))
      (node (ref "R20") (pin "1") (pinfunction "1_1") (pintype "passive"))
    )
    (net (code "62") (name "Net-(IC13-K)") (class "Default")
      (node (ref "IC13") (pin "2") (pinfunction "K_2") (pintype "passive"))
      (node (ref "JP7") (pin "2") (pinfunction "2_2") (pintype "passive"))
    )
    (net (code "63") (name "Net-(IC14-A)") (class "Default")
      (node (ref "IC14") (pin "1") (pinfunction "A_1") (pintype "passive"))
      (node (ref "R24") (pin "1") (pinfunction "1_1") (pintype "passive"))
    )
    (net (code "64") (name "Net-(IC14-E)") (class "Default")
      (node (ref "C26") (pin "2") (pinfunction "2_2") (pintype "passive"))
      (node (ref "IC14") (pin "3") (pinfunction "E_3") (pintype "passive"))
      (node (ref "Q5") (pin "1") (pinfunction "G_1") (pintype "passive"))
      (node (ref "R27") (pin "2") (pinfunction "2_2") (pintype "passive"))
    )
    (net (code "65") (name "Net-(IC15-A)") (class "Default")
      (node (ref "IC15") (pin "1") (pinfunction "A_1") (pintype "passive"))
      (node (ref "R26") (pin "1") (pinfunction "1_1") (pintype "passive"))
    )
    (net (code "66") (name "Net-(IC15-C)") (class "Default")
      (node (ref "IC15") (pin "4") (pinfunction "C_4") (pintype "passive"))
      (node (ref "R25") (pin "1") (pinfunction "1_1") (pintype "passive"))
    )
    (net (code "67") (name "Net-(IC15-K)") (class "Default")
      (node (ref "IC15") (pin "2") (pinfunction "K_2") (pintype "passive"))
      (node (ref "JP7") (pin "1") (pinfunction "1_1") (pintype "passive"))
    )
    (net (code "68") (name "Net-(IC16-A)") (class "Default")
      (node (ref "IC16") (pin "1") (pinfunction "A_1") (pintype "passive"))
      (node (ref "R33") (pin "1") (pinfunction "1_1") (pintype "passive"))
    )
    (net (code "69") (name "Net-(IC16-C)") (class "Default")
      (node (ref "IC16") (pin "4") (pinfunction "C_4") (pintype "passive"))
      (node (ref "R32") (pin "1") (pinfunction "1_1") (pintype "passive"))
    )
    (net (code "70") (name "Net-(IC16-K)") (class "Default")
      (node (ref "IC16") (pin "2") (pinfunction "K_2") (pintype "passive"))
      (node (ref "JP10") (pin "4") (pinfunction "4_4") (pintype "passive"))
    )
    (net (code "71") (name "Net-(IC18-A)") (class "Default")
      (node (ref "IC18") (pin "1") (pinfunction "A_1") (pintype "passive"))
      (node (ref "R36") (pin "1") (pinfunction "1_1") (pintype "passive"))
    )
    (net (code "72") (name "Net-(IC18-C)") (class "Default")
      (node (ref "IC18") (pin "4") (pinfunction "C_4") (pintype "passive"))
      (node (ref "R35") (pin "1") (pinfunction "1_1") (pintype "passive"))
    )
    (net (code "73") (name "Net-(IC18-K)") (class "Default")
      (node (ref "IC18") (pin "2") (pinfunction "K_2") (pintype "passive"))
      (node (ref "JP10") (pin "2") (pinfunction "2_2") (pintype "passive"))
    )
    (net (code "74") (name "Net-(IC19-A)") (class "Default")
      (node (ref "IC19") (pin "1") (pinfunction "A_1") (pintype "passive"))
      (node (ref "R44") (pin "1") (pinfunction "1_1") (pintype "passive"))
    )
    (net (code "75") (name "Net-(IC19-C)") (class "Default")
      (node (ref "IC19") (pin "4") (pinfunction "C_4") (pintype "passive"))
      (node (ref "R43") (pin "1") (pinfunction "1_1") (pintype "passive"))
    )
    (net (code "76") (name "Net-(IC19-K)") (class "Default")
      (node (ref "IC19") (pin "2") (pinfunction "K_2") (pintype "passive"))
      (node (ref "JP12") (pin "4") (pinfunction "4_4") (pintype "passive"))
    )
    (net (code "77") (name "Net-(IC20-A)") (class "Default")
      (node (ref "IC20") (pin "1") (pinfunction "A_1") (pintype "passive"))
      (node (ref "R47") (pin "1") (pinfunction "1_1") (pintype "passive"))
    )
    (net (code "78") (name "Net-(IC20-C)") (class "Default")
      (node (ref "IC20") (pin "4") (pinfunction "C_4") (pintype "passive"))
      (node (ref "R46") (pin "1") (pinfunction "1_1") (pintype "passive"))
    )
    (net (code "79") (name "Net-(IC20-K)") (class "Default")
      (node (ref "IC20") (pin "2") (pinfunction "K_2") (pintype "passive"))
      (node (ref "JP12") (pin "2") (pinfunction "2_2") (pintype "passive"))
    )
    (net (code "80") (name "Net-(Q1-D)") (class "Default")
      (node (ref "JP3") (pin "2") (pinfunction "2_2") (pintype "passive"))
      (node (ref "Q1") (pin "3") (pinfunction "D_3") (pintype "passive"))
    )
    (net (code "81") (name "Net-(Q2-D)") (class "Default")
      (node (ref "JP3") (pin "4") (pinfunction "4_4") (pintype "passive"))
      (node (ref "Q2") (pin "3") (pinfunction "D_3") (pintype "passive"))
    )
    (net (code "82") (name "Net-(Q3-D)") (class "Default")
      (node (ref "JP6") (pin "2") (pinfunction "2_2") (pintype "passive"))
      (node (ref "Q3") (pin "3") (pinfunction "D_3") (pintype "passive"))
    )
    (net (code "83") (name "Net-(Q4-D)") (class "Default")
      (node (ref "JP6") (pin "4") (pinfunction "4_4") (pintype "passive"))
      (node (ref "Q4") (pin "3") (pinfunction "D_3") (pintype "passive"))
    )
    (net (code "84") (name "Net-(Q5-D)") (class "Default")
      (node (ref "JP8") (pin "1") (pinfunction "1_1") (pintype "passive"))
      (node (ref "Q5") (pin "3") (pinfunction "D_3") (pintype "passive"))
    )
    (net (code "85") (name "Net-(R3-Pad1)") (class "Default")
      (node (ref "R3") (pin "1") (pinfunction "1_1") (pintype "passive"))
      (node (ref "TP1") (pin "1") (pinfunction "1_1") (pintype "passive"))
    )
    (net (code "86") (name "Net-(U1-OSC_IN{slash}PD0)") (class "Default")
      (node (ref "C10") (pin "1") (pinfunction "1_1") (pintype "passive"))
      (node (ref "U1") (pin "5") (pinfunction "OSC_IN/PD0_5") (pintype "input"))
      (node (ref "X1") (pin "1") (pinfunction "1_1") (pintype "passive"))
    )
    (net (code "87") (name "Net-(U1-OSC_OUT{slash}PD1)") (class "Default")
      (node (ref "C14") (pin "1") (pinfunction "1_1") (pintype "passive"))
      (node (ref "U1") (pin "6") (pinfunction "OSC_OUT/PD1_6") (pintype "output"))
      (node (ref "X1") (pin "3") (pinfunction "3_3") (pintype "passive"))
    )
    (net (code "88") (name "Net-(U1-PC14-OSC32_IN)") (class "Default")
      (node (ref "C11") (pin "2") (pinfunction "2_2") (pintype "passive"))
      (node (ref "U1") (pin "3") (pinfunction "PC14-OSC32_IN_3") (pintype "bidirectional"))
      (node (ref "X2") (pin "2") (pinfunction "2_2") (pintype "passive"))
    )
    (net (code "89") (name "Net-(U1-PC15-OSC32_OUT)") (class "Default")
      (node (ref "C15") (pin "2") (pinfunction "2_2") (pintype "passive"))
      (node (ref "U1") (pin "4") (pinfunction "PC15-OSC32_OUT_4") (pintype "bidirectional"))
      (node (ref "X2") (pin "1") (pinfunction "1_1") (pintype "passive"))
    )
    (net (code "90") (name "Net-(V1-Vout)") (class "Default")
      (node (ref "C7") (pin "1") (pinfunction "1_1") (pintype "passive"))
      (node (ref "C8") (pin "2") (pinfunction "2_2") (pintype "passive"))
      (node (ref "R49") (pin "1") (pinfunction "1_1") (pintype "passive"))
      (node (ref "V1") (pin "2") (pinfunction "Vout_2") (pintype "passive"))
    )
    (net (code "91") (name "Net-(VD3-K)") (class "Default")
      (node (ref "R38") (pin "2") (pinfunction "2_2") (pintype "passive"))
      (node (ref "VD3") (pin "2") (pinfunction "K_2") (pintype "passive"))
    )
    (net (code "92") (name "VCC-5V") (class "Default")
      (node (ref "IC3") (pin "4") (pinfunction "V-_4") (pintype "power_in"))
      (node (ref "IC4") (pin "4") (pinfunction "V-_4") (pintype "power_in"))
      (node (ref "IC6") (pin "4") (pinfunction "V-_4") (pintype "power_in"))
      (node (ref "JP1") (pin "5") (pinfunction "5_5") (pintype "passive"))
    )
    (net (code "93") (name "VCC-12V") (class "Default")
      (node (ref "IC9") (pin "4") (pinfunction "VSS_4") (pintype "passive"))
      (node (ref "JP1") (pin "4") (pinfunction "4_4") (pintype "passive"))
    )
    (net (code "94") (name "VCC3V3") (class "Default")
      (node (ref "C1") (pin "2") (pinfunction "2_2") (pintype "passive"))
      (node (ref "C18") (pin "2") (pinfunction "2_2") (pintype "passive"))
      (node (ref "C20") (pin "2") (pinfunction "2_2") (pintype "passive"))
      (node (ref "C21") (pin "2") (pinfunction "2_2") (pintype "passive"))
      (node (ref "C22") (pin "2") (pinfunction "2_2") (pintype "passive"))
      (node (ref "C24") (pin "1") (pinfunction "1_1") (pintype "passive"))
      (node (ref "IC1") (pin "8") (pinfunction "VCC_8") (pintype "passive"))
      (node (ref "IC17") (pin "3") (pinfunction "VDD_3") (pintype "passive"))
      (node (ref "JP11") (pin "2") (pinfunction "2_2") (pintype "passive"))
      (node (ref "JP9") (pin "3") (pinfunction "3_3") (pintype "passive"))
      (node (ref "R1") (pin "2") (pinfunction "2_2") (pintype "passive"))
      (node (ref "R14") (pin "2") (pinfunction "2_2") (pintype "passive"))
      (node (ref "R20") (pin "2") (pinfunction "2_2") (pintype "passive"))
      (node (ref "R25") (pin "2") (pinfunction "2_2") (pintype "passive"))
      (node (ref "R32") (pin "2") (pinfunction "2_2") (pintype "passive"))
      (node (ref "R35") (pin "2") (pinfunction "2_2") (pintype "passive"))
      (node (ref "R39") (pin "1") (pinfunction "1_1") (pintype "passive"))
      (node (ref "R40") (pin "1") (pinfunction "1_1") (pintype "passive"))
      (node (ref "R43") (pin "2") (pinfunction "2_2") (pintype "passive"))
      (node (ref "R46") (pin "2") (pinfunction "2_2") (pintype "passive"))
      (node (ref "R49") (pin "2") (pinfunction "2_2") (pintype "passive"))
      (node (ref "R5") (pin "2") (pinfunction "2_2") (pintype "passive"))
      (node (ref "R50") (pin "2") (pinfunction "2_2") (pintype "passive"))
      (node (ref "R6") (pin "2") (pinfunction "2_2") (pintype "passive"))
      (node (ref "U1") (pin "24") (pinfunction "VDD_1_24") (pintype "power_in"))
      (node (ref "U1") (pin "36") (pinfunction "VDD_2_36") (pintype "power_in"))
      (node (ref "U1") (pin "48") (pinfunction "VDD_3_48") (pintype "power_in"))
      (node (ref "U1") (pin "9") (pinfunction "VDDA_9") (pintype "power_in"))
    )
    (net (code "95") (name "VCC5V") (class "Default")
      (node (ref "C5") (pin "2") (pinfunction "2_2") (pintype "passive"))
      (node (ref "C6") (pin "1") (pinfunction "1_1") (pintype "passive"))
      (node (ref "IC3") (pin "8") (pinfunction "V+_8") (pintype "power_in"))
      (node (ref "IC4") (pin "8") (pinfunction "V+_8") (pintype "power_in"))
      (node (ref "IC6") (pin "8") (pinfunction "V+_8") (pintype "power_in"))
      (node (ref "JP1") (pin "2") (pinfunction "2_2") (pintype "passive"))
      (node (ref "V1") (pin "3") (pinfunction "Vin_3") (pintype "passive"))
    )
    (net (code "96") (name "VCC12V") (class "Default")
      (node (ref "IC10") (pin "4") (pinfunction "C_4") (pintype "passive"))
      (node (ref "IC12") (pin "4") (pinfunction "C_4") (pintype "passive"))
      (node (ref "IC14") (pin "4") (pinfunction "C_4") (pintype "passive"))
      (node (ref "IC5") (pin "4") (pinfunction "C_4") (pintype "passive"))
      (node (ref "IC7") (pin "4") (pinfunction "C_4") (pintype "passive"))
      (node (ref "IC8") (pin "4") (pinfunction "C_4") (pintype "passive"))
      (node (ref "IC9") (pin "6") (pinfunction "VDD_6") (pintype "passive"))
      (node (ref "JP1") (pin "1") (pinfunction "1_1") (pintype "passive"))
      (node (ref "JP3") (pin "1") (pinfunction "1_1") (pintype "passive"))
      (node (ref "JP3") (pin "3") (pinfunction "3_3") (pintype "passive"))
      (node (ref "JP5") (pin "1") (pinfunction "1_1") (pintype "passive"))
      (node (ref "JP6") (pin "1") (pinfunction "1_1") (pintype "passive"))
      (node (ref "JP6") (pin "3") (pinfunction "3_3") (pintype "passive"))
      (node (ref "JP7") (pin "4") (pinfunction "4_4") (pintype "passive"))
      (node (ref "JP8") (pin "2") (pinfunction "2_2") (pintype "passive"))
      (node (ref "R16") (pin "2") (pinfunction "2_2") (pintype "passive"))
      (node (ref "R21") (pin "2") (pinfunction "2_2") (pintype "passive"))
      (node (ref "R26") (pin "2") (pinfunction "2_2") (pintype "passive"))
      (node (ref "R33") (pin "2") (pinfunction "2_2") (pintype "passive"))
      (node (ref "R36") (pin "2") (pinfunction "2_2") (pintype "passive"))
      (node (ref "R44") (pin "2") (pinfunction "2_2") (pintype "passive"))
      (node (ref "R47") (pin "2") (pinfunction "2_2") (pintype "passive"))
    )
    (net (code "97") (name "unconnected-(IC3B-OUT-Pad7)") (class "Default")
      (node (ref "IC3") (pin "7") (pinfunction "OUT_7") (pintype "output+no_connect"))
    )
    (net (code "98") (name "unconnected-(IC6B-OUT-Pad7)") (class "Default")
      (node (ref "IC6") (pin "7") (pinfunction "OUT_7") (pintype "output+no_connect"))
    )
    (net (code "99") (name "unconnected-(IC9-NC-Pad2)") (class "Default")
      (node (ref "IC9") (pin "2") (pinfunction "NC_2") (pintype "passive"))
    )
    (net (code "100") (name "unconnected-(U1-PB7-Pad43)") (class "Default")
      (node (ref "U1") (pin "43") (pinfunction "PB7_43") (pintype "bidirectional"))
    )
    (net (code "101") (name "unconnected-(U1-PB8-Pad45)") (class "Default")
      (node (ref "U1") (pin "45") (pinfunction "PB8_45") (pintype "bidirectional"))
    )
    (net (code "102") (name "unconnected-(U1-PB9-Pad46)") (class "Default")
      (node (ref "U1") (pin "46") (pinfunction "PB9_46") (pintype "bidirectional"))
    )
    (net (code "103") (name "unconnected-(U1-PC13-TAMPER-RTC-Pad2)") (class "Default")
      (node (ref "U1") (pin "2") (pinfunction "PC13-TAMPER-RTC_2") (pintype "bidirectional"))
    )
    (net (code "104") (name "unconnected-(U1-VBAT-Pad1)") (class "Default")
      (node (ref "U1") (pin "1") (pinfunction "VBAT_1") (pintype "power_in+no_connect"))
    )
  )
)
